# ponte_h_mosfet.net
KiCad netlist of a schematic drawn in EAGLE
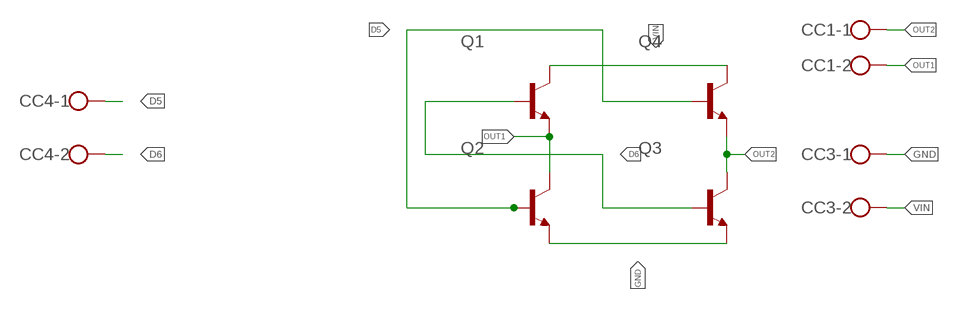
[diagram p0: schematic, sheet 1]

(export (version "E")
  (design (tool "Eeschema 10.0.6"))
  (components
    (comp (ref "CC1")
      (value "W237-102")
      (footprint "eagle-import:W237-102")
      (fields (field (name "MPN") "237-102"))
      (libsource (lib "eagle-import") (part "W237-102"))
    )
    (comp (ref "CC3")
      (value "W237-102")
      (footprint "eagle-import:W237-102")
      (fields (field (name "MPN") "237-102"))
      (libsource (lib "eagle-import") (part "W237-102"))
    )
    (comp (ref "CC4")
      (value "W237-102")
      (footprint "eagle-import:W237-102")
      (fields (field (name "MPN") "237-102"))
      (libsource (lib "eagle-import") (part "W237-102"))
    )
    (comp (ref "Q1")
      (value "-NPN-TO220V")
      (footprint "eagle-import:TO220V")
      (libsource (lib "eagle-import") (part "-NPN-TO220V"))
    )
    (comp (ref "Q2")
      (value "-NPN-TO220V")
      (footprint "eagle-import:TO220V")
      (libsource (lib "eagle-import") (part "-NPN-TO220V"))
    )
    (comp (ref "Q3")
      (value "-NPN-TO220V")
      (footprint "eagle-import:TO220V")
      (libsource (lib "eagle-import") (part "-NPN-TO220V"))
    )
    (comp (ref "Q4")
      (value "-NPN-TO220V")
      (footprint "eagle-import:TO220V")
      (libsource (lib "eagle-import") (part "-NPN-TO220V"))
    )
  )
  (nets
    (net (code "1") (name "D5") (class "Default")
      (node (ref "CC4") (pin "1") (pinfunction "KL_1") (pintype "passive"))
      (node (ref "Q2") (pin "1") (pinfunction "B_1") (pintype "passive"))
      (node (ref "Q4") (pin "1") (pinfunction "B_1") (pintype "passive"))
    )
    (net (code "2") (name "D6") (class "Default")
      (node (ref "CC4") (pin "2") (pinfunction "KL_2") (pintype "passive"))
      (node (ref "Q1") (pin "1") (pinfunction "B_1") (pintype "passive"))
      (node (ref "Q3") (pin "1") (pinfunction "B_1") (pintype "passive"))
    )
    (net (code "3") (name "GND") (class "Default")
      (node (ref "CC3") (pin "1") (pinfunction "KL_1") (pintype "passive"))
      (node (ref "Q2") (pin "3") (pinfunction "E_3") (pintype "passive"))
      (node (ref "Q3") (pin "3") (pinfunction "E_3") (pintype "passive"))
    )
    (net (code "4") (name "OUT1") (class "Default")
      (node (ref "CC1") (pin "2") (pinfunction "KL_2") (pintype "passive"))
      (node (ref "Q1") (pin "3") (pinfunction "E_3") (pintype "passive"))
      (node (ref "Q2") (pin "2") (pinfunction "C_2") (pintype "passive"))
    )
    (net (code "5") (name "OUT2") (class "Default")
      (node (ref "CC1") (pin "1") (pinfunction "KL_1") (pintype "passive"))
      (node (ref "Q3") (pin "2") (pinfunction "C_2") (pintype "passive"))
      (node (ref "Q4") (pin "3") (pinfunction "E_3") (pintype "passive"))
    )
    (net (code "6") (name "VIN") (class "Default")
      (node (ref "CC3") (pin "2") (pinfunction "KL_2") (pintype "passive"))
      (node (ref "Q1") (pin "2") (pinfunction "C_2") (pintype "passive"))
      (node (ref "Q4") (pin "2") (pinfunction "C_2") (pintype "passive"))
    )
  )
)
